# 14DoF_MPU9150.net
KiCad netlist of a schematic drawn in EAGLE
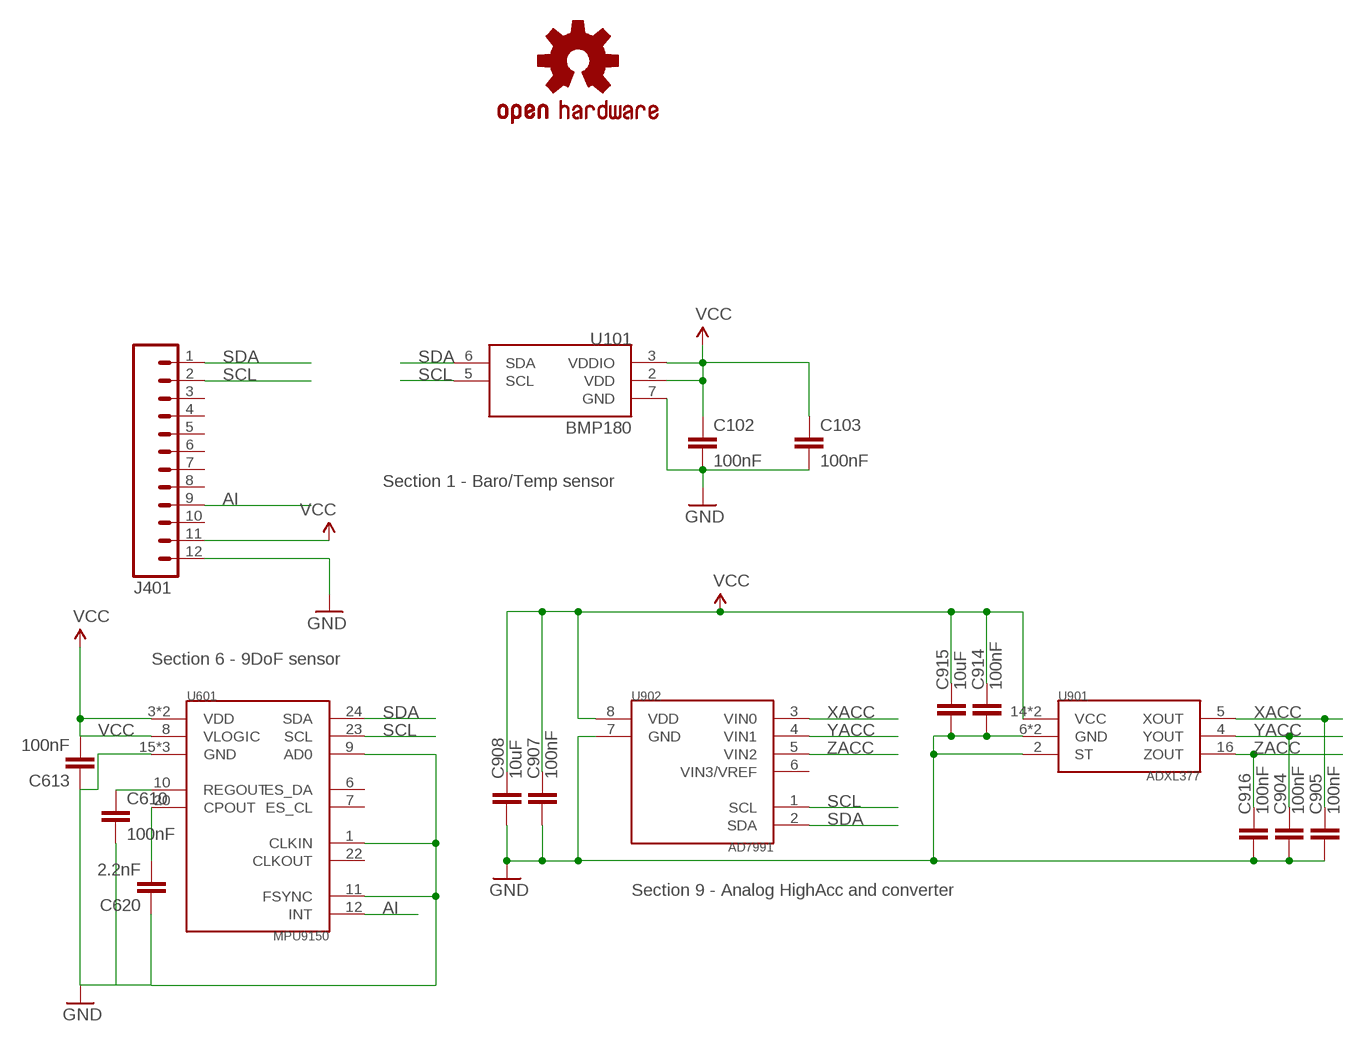
[diagram p0: schematic, sheet 1]

(export (version "E")
  (design (tool "Eeschema 10.0.6"))
  (components
    (comp (ref "C102")
      (value "100nF")
      (footprint "eagle-import:0603-CAP")
      (libsource (lib "eagle-import") (part "CAP0603-CAP"))
    )
    (comp (ref "C103")
      (value "100nF")
      (footprint "eagle-import:0603-CAP")
      (libsource (lib "eagle-import") (part "CAP0603-CAP"))
    )
    (comp (ref "C610")
      (value "100nF")
      (footprint "eagle-import:0603-CAP")
      (libsource (lib "eagle-import") (part "CAP0603-CAP"))
    )
    (comp (ref "C613")
      (value "100nF")
      (footprint "eagle-import:0603-CAP")
      (libsource (lib "eagle-import") (part "CAP0603-CAP"))
    )
    (comp (ref "C620")
      (value "2.2nF")
      (footprint "eagle-import:0603-CAP")
      (libsource (lib "eagle-import") (part "CAP0603-CAP"))
    )
    (comp (ref "C904")
      (value "100nF")
      (footprint "eagle-import:0603-CAP")
      (libsource (lib "eagle-import") (part "CAP0603-CAP"))
    )
    (comp (ref "C905")
      (value "100nF")
      (footprint "eagle-import:0603-CAP")
      (libsource (lib "eagle-import") (part "CAP0603-CAP"))
    )
    (comp (ref "C907")
      (value "100nF")
      (footprint "eagle-import:0603-CAP")
      (libsource (lib "eagle-import") (part "CAP0603-CAP"))
    )
    (comp (ref "C908")
      (value "10uF")
      (footprint "eagle-import:0603-CAP")
      (libsource (lib "eagle-import") (part "CAP0603-CAP"))
    )
    (comp (ref "C914")
      (value "100nF")
      (footprint "eagle-import:0603-CAP")
      (libsource (lib "eagle-import") (part "CAP0603-CAP"))
    )
    (comp (ref "C915")
      (value "10uF")
      (footprint "eagle-import:0603-CAP")
      (libsource (lib "eagle-import") (part "CAP0603-CAP"))
    )
    (comp (ref "C916")
      (value "100nF")
      (footprint "eagle-import:0603-CAP")
      (libsource (lib "eagle-import") (part "CAP0603-CAP"))
    )
    (comp (ref "J401")
      (value "M12PTH")
      (footprint "eagle-import:1X12")
      (libsource (lib "eagle-import") (part "M12PTH"))
    )
    (comp (ref "U$2")
      (value "OSHW-LOGOS")
      (footprint "eagle-import:OSHW-LOGO-S")
      (libsource (lib "eagle-import") (part "OSHW-LOGOS"))
    )
    (comp (ref "U101")
      (value "BMP180")
      (footprint "eagle-import:BMP180")
      (libsource (lib "eagle-import") (part "BMP180"))
    )
    (comp (ref "U601")
      (value "MPU9150")
      (footprint "eagle-import:LLGA24")
      (libsource (lib "eagle-import") (part "MPU9150"))
    )
    (comp (ref "U901")
      (value "ADXL377")
      (footprint "eagle-import:ADXL377")
      (libsource (lib "eagle-import") (part "ADXL377"))
    )
    (comp (ref "U902")
      (value "AD7991")
      (footprint "eagle-import:SOT-23-8")
      (libsource (lib "eagle-import") (part "AD799X"))
    )
  )
  (nets
    (net (code "1") (name "/AI") (class "Default")
      (node (ref "J401") (pin "9") (pinfunction "9_9") (pintype "passive"))
      (node (ref "U601") (pin "12") (pinfunction "INT_12") (pintype "bidirectional"))
    )
    (net (code "2") (name "/SCL") (class "Default")
      (node (ref "J401") (pin "2") (pinfunction "2_2") (pintype "passive"))
      (node (ref "U101") (pin "5") (pinfunction "SCL_5") (pintype "input"))
      (node (ref "U601") (pin "23") (pinfunction "SCL_23") (pintype "bidirectional"))
      (node (ref "U902") (pin "1") (pinfunction "SCL_1") (pintype "bidirectional"))
    )
    (net (code "3") (name "/SDA") (class "Default")
      (node (ref "J401") (pin "1") (pinfunction "1_1") (pintype "passive"))
      (node (ref "U101") (pin "6") (pinfunction "SDA_6") (pintype "bidirectional"))
      (node (ref "U601") (pin "24") (pinfunction "SDA_24") (pintype "bidirectional"))
      (node (ref "U902") (pin "2") (pinfunction "SDA_2") (pintype "bidirectional"))
    )
    (net (code "4") (name "/XACC") (class "Default")
      (node (ref "C905") (pin "1") (pinfunction "1_1") (pintype "passive"))
      (node (ref "U901") (pin "5") (pinfunction "XOUT_5") (pintype "bidirectional"))
      (node (ref "U902") (pin "3") (pinfunction "VIN0_3") (pintype "bidirectional"))
    )
    (net (code "5") (name "/YACC") (class "Default")
      (node (ref "C904") (pin "1") (pinfunction "1_1") (pintype "passive"))
      (node (ref "U901") (pin "4") (pinfunction "YOUT_4") (pintype "bidirectional"))
      (node (ref "U902") (pin "4") (pinfunction "VIN1_4") (pintype "bidirectional"))
    )
    (net (code "6") (name "/ZACC") (class "Default")
      (node (ref "C916") (pin "1") (pinfunction "1_1") (pintype "passive"))
      (node (ref "U901") (pin "16") (pinfunction "ZOUT_16") (pintype "bidirectional"))
      (node (ref "U902") (pin "5") (pinfunction "VIN2_5") (pintype "bidirectional"))
    )
    (net (code "7") (name "GND") (class "Default")
      (node (ref "C102") (pin "2") (pinfunction "2_2") (pintype "passive"))
      (node (ref "C103") (pin "2") (pinfunction "2_2") (pintype "passive"))
      (node (ref "C610") (pin "2") (pinfunction "2_2") (pintype "passive"))
      (node (ref "C613") (pin "1") (pinfunction "1_1") (pintype "passive"))
      (node (ref "C620") (pin "1") (pinfunction "1_1") (pintype "passive"))
      (node (ref "C904") (pin "2") (pinfunction "2_2") (pintype "passive"))
      (node (ref "C905") (pin "2") (pinfunction "2_2") (pintype "passive"))
      (node (ref "C907") (pin "2") (pinfunction "2_2") (pintype "passive"))
      (node (ref "C908") (pin "2") (pinfunction "2_2") (pintype "passive"))
      (node (ref "C914") (pin "2") (pinfunction "2_2") (pintype "passive"))
      (node (ref "C915") (pin "2") (pinfunction "2_2") (pintype "passive"))
      (node (ref "C916") (pin "2") (pinfunction "2_2") (pintype "passive"))
      (node (ref "J401") (pin "12") (pinfunction "12_12") (pintype "passive"))
      (node (ref "U101") (pin "7") (pinfunction "GND_7") (pintype "power_in"))
      (node (ref "U601") (pin "1") (pinfunction "CLKIN_1") (pintype "bidirectional"))
      (node (ref "U601") (pin "11") (pinfunction "FSYNC_11") (pintype "bidirectional"))
      (node (ref "U601") (pin "15") (pinfunction "GND_15") (pintype "bidirectional"))
      (node (ref "U601") (pin "17") (pinfunction "GND_17") (pintype "bidirectional"))
      (node (ref "U601") (pin "18") (pinfunction "GND_18") (pintype "bidirectional"))
      (node (ref "U601") (pin "9") (pinfunction "AD0_9") (pintype "bidirectional"))
      (node (ref "U901") (pin "2") (pinfunction "ST_2") (pintype "bidirectional"))
      (node (ref "U901") (pin "6") (pinfunction "GND_6") (pintype "bidirectional"))
      (node (ref "U901") (pin "7") (pinfunction "GND_7") (pintype "bidirectional"))
      (node (ref "U902") (pin "7") (pinfunction "GND_7") (pintype "bidirectional"))
    )
    (net (code "8") (name "Net-(U601-CPOUT)") (class "Default")
      (node (ref "C620") (pin "2") (pinfunction "2_2") (pintype "passive"))
      (node (ref "U601") (pin "20") (pinfunction "CPOUT_20") (pintype "bidirectional"))
    )
    (net (code "9") (name "Net-(U601-REGOUT)") (class "Default")
      (node (ref "C610") (pin "1") (pinfunction "1_1") (pintype "passive"))
      (node (ref "U601") (pin "10") (pinfunction "REGOUT_10") (pintype "bidirectional"))
    )
    (net (code "10") (name "VCC") (class "Default")
      (node (ref "C102") (pin "1") (pinfunction "1_1") (pintype "passive"))
      (node (ref "C103") (pin "1") (pinfunction "1_1") (pintype "passive"))
      (node (ref "C613") (pin "2") (pinfunction "2_2") (pintype "passive"))
      (node (ref "C907") (pin "1") (pinfunction "1_1") (pintype "passive"))
      (node (ref "C908") (pin "1") (pinfunction "1_1") (pintype "passive"))
      (node (ref "C914") (pin "1") (pinfunction "1_1") (pintype "passive"))
      (node (ref "C915") (pin "1") (pinfunction "1_1") (pintype "passive"))
      (node (ref "J401") (pin "11") (pinfunction "11_11") (pintype "passive"))
      (node (ref "U101") (pin "2") (pinfunction "VDD_2") (pintype "power_in"))
      (node (ref "U101") (pin "3") (pinfunction "VDDIO_3") (pintype "power_in"))
      (node (ref "U601") (pin "13") (pinfunction "VDD_13") (pintype "bidirectional"))
      (node (ref "U601") (pin "3") (pinfunction "VDD_3") (pintype "bidirectional"))
      (node (ref "U601") (pin "8") (pinfunction "VLOGIC_8") (pintype "bidirectional"))
      (node (ref "U901") (pin "14") (pinfunction "VCC_14") (pintype "bidirectional"))
      (node (ref "U901") (pin "15") (pinfunction "VCC_15") (pintype "bidirectional"))
      (node (ref "U902") (pin "8") (pinfunction "VDD_8") (pintype "bidirectional"))
    )
    (net (code "11") (name "unconnected-(J401-Pad3)") (class "Default")
      (node (ref "J401") (pin "3") (pinfunction "3_3") (pintype "passive"))
    )
    (net (code "12") (name "unconnected-(J401-Pad4)") (class "Default")
      (node (ref "J401") (pin "4") (pinfunction "4_4") (pintype "passive"))
    )
    (net (code "13") (name "unconnected-(J401-Pad5)") (class "Default")
      (node (ref "J401") (pin "5") (pinfunction "5_5") (pintype "passive"))
    )
    (net (code "14") (name "unconnected-(J401-Pad6)") (class "Default")
      (node (ref "J401") (pin "6") (pinfunction "6_6") (pintype "passive"))
    )
    (net (code "15") (name "unconnected-(J401-Pad7)") (class "Default")
      (node (ref "J401") (pin "7") (pinfunction "7_7") (pintype "passive"))
    )
    (net (code "16") (name "unconnected-(J401-Pad8)") (class "Default")
      (node (ref "J401") (pin "8") (pinfunction "8_8") (pintype "passive"))
    )
    (net (code "17") (name "unconnected-(J401-Pad10)") (class "Default")
      (node (ref "J401") (pin "10") (pinfunction "10_10") (pintype "passive"))
    )
    (net (code "18") (name "unconnected-(U601-CLKOUT-Pad22)") (class "Default")
      (node (ref "U601") (pin "22") (pinfunction "CLKOUT_22") (pintype "bidirectional"))
    )
    (net (code "19") (name "unconnected-(U601-ES_CL-Pad7)") (class "Default")
      (node (ref "U601") (pin "7") (pinfunction "ES_CL_7") (pintype "bidirectional"))
    )
    (net (code "20") (name "unconnected-(U601-ES_DA-Pad6)") (class "Default")
      (node (ref "U601") (pin "6") (pinfunction "ES_DA_6") (pintype "bidirectional"))
    )
    (net (code "21") (name "unconnected-(U902-VIN3{slash}VREF-Pad6)") (class "Default")
      (node (ref "U902") (pin "6") (pinfunction "VIN3/VREF_6") (pintype "bidirectional"))
    )
  )
)
